# LoRa_Node.net
KiCad netlist of a schematic drawn in Altium Designer
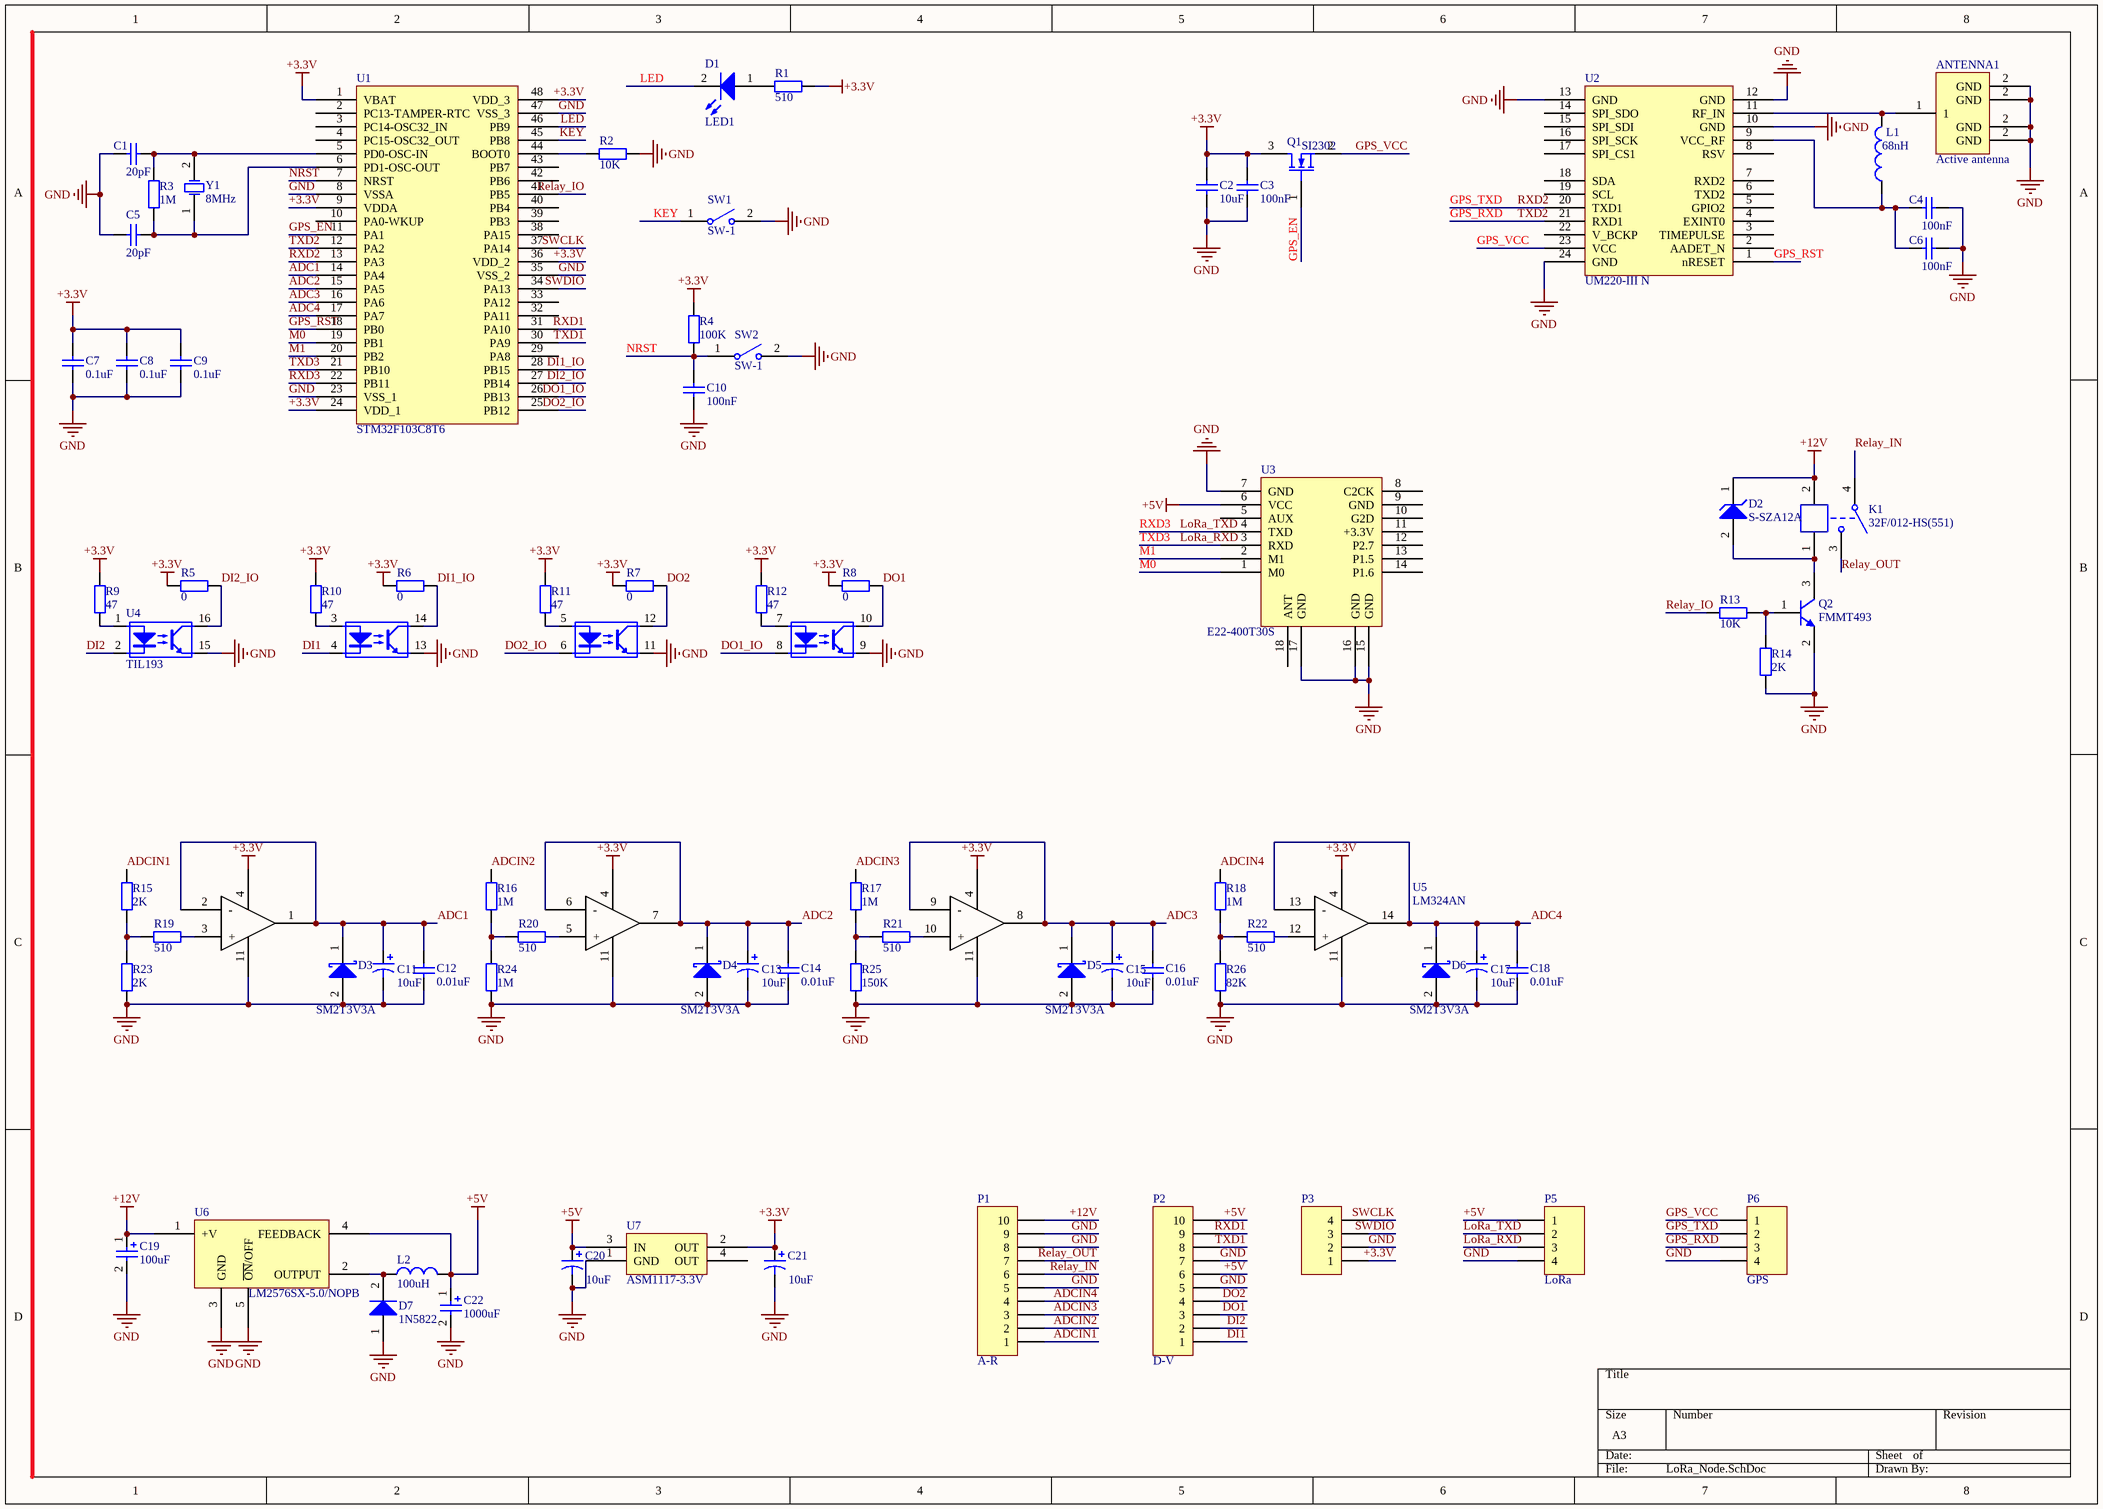
[diagram p0: LoRa_Node.SchDoc]

(export (version "E")
  (design (tool "Eeschema 10.0.6"))
  (components
    (comp (ref "ANTENNA1")
      (value "Active antenna")
      (footprint "SMA-W")
      (libsource (lib "WuRenSouJiu") (part "Active antenna"))
    )
    (comp (ref "C1")
      (value "20pF")
      (footprint "0603C")
      (description "Capacitor")
      (fields (field (name "Comment") "Cap8") (field (name "PUBLISHER") "Altium Limited"))
      (libsource (lib "Miscellaneous Devices") (part "Cap"))
    )
    (comp (ref "C2")
      (value "10uF")
      (footprint "0603C")
      (description "Capacitor")
      (fields (field (name "Comment") "Cap15") (field (name "PUBLISHER") "Altium Limited"))
      (libsource (lib "Miscellaneous Devices") (part "Cap"))
    )
    (comp (ref "C3")
      (value "100nF")
      (footprint "0603C")
      (description "Capacitor")
      (fields (field (name "Comment") "Cap16") (field (name "PUBLISHER") "Altium Limited"))
      (libsource (lib "Miscellaneous Devices") (part "Cap"))
    )
    (comp (ref "C4")
      (value "100nF")
      (footprint "0603C")
      (description "Capacitor")
      (fields (field (name "Comment") "Cap17") (field (name "PUBLISHER") "Altium Limited"))
      (libsource (lib "Miscellaneous Devices") (part "Cap"))
    )
    (comp (ref "C5")
      (value "20pF")
      (footprint "0603C")
      (description "Capacitor")
      (fields (field (name "Comment") "Cap9") (field (name "PUBLISHER") "Altium Limited"))
      (libsource (lib "Miscellaneous Devices") (part "Cap"))
    )
    (comp (ref "C6")
      (value "100nF")
      (footprint "0603C")
      (description "Capacitor")
      (fields (field (name "Comment") "Cap18") (field (name "PUBLISHER") "Altium Limited"))
      (libsource (lib "Miscellaneous Devices") (part "Cap"))
    )
    (comp (ref "C7")
      (value "0.1uF")
      (footprint "0603C")
      (description "Capacitor")
      (fields (field (name "Comment") "Cap11") (field (name "PUBLISHER") "Altium Limited"))
      (libsource (lib "Miscellaneous Devices") (part "Cap"))
    )
    (comp (ref "C8")
      (value "0.1uF")
      (footprint "0603C")
      (description "Capacitor")
      (fields (field (name "Comment") "Cap12") (field (name "PUBLISHER") "Altium Limited"))
      (libsource (lib "Miscellaneous Devices") (part "Cap"))
    )
    (comp (ref "C9")
      (value "0.1uF")
      (footprint "0603C")
      (description "Capacitor")
      (fields (field (name "Comment") "Cap13") (field (name "PUBLISHER") "Altium Limited"))
      (libsource (lib "Miscellaneous Devices") (part "Cap"))
    )
    (comp (ref "C10")
      (value "100nF")
      (footprint "0603C")
      (description "Capacitor")
      (fields (field (name "Comment") "Cap10") (field (name "PUBLISHER") "Altium Limited"))
      (libsource (lib "Miscellaneous Devices") (part "Cap"))
    )
    (comp (ref "C11")
      (value "10uF")
      (footprint "0603C")
      (description "Polarized Capacitor (Radial)")
      (fields (field (name "PUBLISHER") "Altium Limited"))
      (libsource (lib "Miscellaneous Devices") (part "Cap Pol1"))
    )
    (comp (ref "C12")
      (value "0.01uF")
      (footprint "0603C")
      (description "无极性电容")
      (fields (field (name "Comment") "Cap") (field (name "PUBLISHER") "Altium Limited"))
      (libsource (lib "18-常用器件") (part "Cap"))
    )
    (comp (ref "C13")
      (value "10uF")
      (footprint "0603C")
      (description "Polarized Capacitor (Radial)")
      (fields (field (name "PUBLISHER") "Altium Limited"))
      (libsource (lib "Miscellaneous Devices") (part "Cap Pol1"))
    )
    (comp (ref "C14")
      (value "0.01uF")
      (footprint "0603C")
      (description "无极性电容")
      (fields (field (name "Comment") "Cap") (field (name "PUBLISHER") "Altium Limited"))
      (libsource (lib "18-常用器件") (part "Cap"))
    )
    (comp (ref "C15")
      (value "10uF")
      (footprint "0603C")
      (description "Polarized Capacitor (Radial)")
      (fields (field (name "PUBLISHER") "Altium Limited"))
      (libsource (lib "Miscellaneous Devices") (part "Cap Pol1"))
    )
    (comp (ref "C16")
      (value "0.01uF")
      (footprint "0603C")
      (description "无极性电容")
      (fields (field (name "Comment") "Cap") (field (name "PUBLISHER") "Altium Limited"))
      (libsource (lib "18-常用器件") (part "Cap"))
    )
    (comp (ref "C17")
      (value "10uF")
      (footprint "0603C")
      (description "Polarized Capacitor (Radial)")
      (fields (field (name "PUBLISHER") "Altium Limited"))
      (libsource (lib "Miscellaneous Devices") (part "Cap Pol1"))
    )
    (comp (ref "C18")
      (value "0.01uF")
      (footprint "0603C")
      (description "无极性电容")
      (fields (field (name "Comment") "Cap") (field (name "PUBLISHER") "Altium Limited"))
      (libsource (lib "18-常用器件") (part "Cap"))
    )
    (comp (ref "C19")
      (value "100uF")
      (footprint "100uF-16V")
      (description "Polarized Capacitor (Axial)")
      (fields (field (name "PUBLISHER") "Altium Limited"))
      (libsource (lib "Miscellaneous Devices") (part "Cap Pol2"))
    )
    (comp (ref "C20")
      (value "10uF")
      (footprint "0603C")
      (description "Polarized Capacitor (Radial)")
      (fields (field (name "PUBLISHER") "Altium Limited"))
      (libsource (lib "Miscellaneous Devices") (part "Cap Pol1"))
    )
    (comp (ref "C21")
      (value "10uF")
      (footprint "0603C")
      (description "Polarized Capacitor (Radial)")
      (fields (field (name "PUBLISHER") "Altium Limited"))
      (libsource (lib "Miscellaneous Devices") (part "Cap Pol1"))
    )
    (comp (ref "C22")
      (value "1000uF")
      (footprint "1000uF-6.3V")
      (description "Polarized Capacitor (Axial)")
      (fields (field (name "PUBLISHER") "Altium Limited"))
      (libsource (lib "Miscellaneous Devices") (part "Cap Pol2"))
    )
    (comp (ref "D1")
      (value "LED1")
      (footprint "D0603")
      (description "Typical RED GaAs LED")
      (fields (field (name "PUBLISHER") "Altium Limited"))
      (libsource (lib "Miscellaneous Devices") (part "LED1"))
    )
    (comp (ref "D2")
      (value "S-SZA12A")
      (footprint "S-SZA12A")
      (description "Zener Diode")
      (fields (field (name "PUBLISHER") "Altium Limited"))
      (libsource (lib "Miscellaneous Devices") (part "D Zener"))
    )
    (comp (ref "D3")
      (value "SM2T3V3A")
      (footprint "3.3V稳压二极管(LMSZ5226BT1G)")
      (description "Schottky Rectifier")
      (fields (field (name "PUBLISHER") "Altium Limited"))
      (libsource (lib "Miscellaneous Devices") (part "Diode 10TQ035"))
    )
    (comp (ref "D4")
      (value "SM2T3V3A")
      (footprint "3.3V稳压二极管(LMSZ5226BT1G)")
      (description "Schottky Rectifier")
      (fields (field (name "PUBLISHER") "Altium Limited"))
      (libsource (lib "Miscellaneous Devices") (part "Diode 10TQ035"))
    )
    (comp (ref "D5")
      (value "SM2T3V3A")
      (footprint "3.3V稳压二极管(LMSZ5226BT1G)")
      (description "Schottky Rectifier")
      (fields (field (name "PUBLISHER") "Altium Limited"))
      (libsource (lib "Miscellaneous Devices") (part "Diode 10TQ035"))
    )
    (comp (ref "D6")
      (value "SM2T3V3A")
      (footprint "3.3V稳压二极管(LMSZ5226BT1G)")
      (description "Schottky Rectifier")
      (fields (field (name "PUBLISHER") "Altium Limited"))
      (libsource (lib "Miscellaneous Devices") (part "Diode 10TQ035"))
    )
    (comp (ref "D7")
      (value "1N5822")
      (footprint "DO-201AD")
      (description "3 Amp Medium Power Silicon Rectifier Diode")
      (fields (field (name "PUBLISHER") "Altium Limited"))
      (libsource (lib "Miscellaneous Devices") (part "Diode 1N5408"))
    )
    (comp (ref "K1")
      (value "32F/012-HS(551)")
      (footprint "32F/012-HS（551）")
      (libsource (lib "7.1   - 继电器") (part "32F/012-HS(551)"))
    )
    (comp (ref "L1")
      (value "68nH")
      (footprint "0603L")
      (description "Inductor")
      (fields (field (name "Comment") "Inductor3") (field (name "PUBLISHER") "Altium Limited"))
      (libsource (lib "Miscellaneous Devices") (part "Inductor"))
    )
    (comp (ref "L2")
      (value "100uH")
      (footprint "L0805")
      (description "电感")
      (fields (field (name "Comment") "Inductor") (field (name "PUBLISHER") "Altium Limited"))
      (libsource (lib "18-常用器件") (part "Inductor"))
    )
    (comp (ref "P1")
      (value "A-R")
      (footprint "HDR2.54-LI-10P")
      (description "Header, 10-Pin")
      (fields (field (name "PUBLISHER") "Altium Limited"))
      (libsource (lib "Miscellaneous Connectors") (part "MHDR1X10"))
    )
    (comp (ref "P2")
      (value "D-V")
      (footprint "HDR2.54-LI-10P")
      (description "Header, 10-Pin")
      (fields (field (name "PUBLISHER") "Altium Limited"))
      (libsource (lib "Miscellaneous Connectors") (part "MHDR1X10"))
    )
    (comp (ref "P3")
      (value "Header 4")
      (footprint "HDR2.54-LI-4P")
      (description "接插件")
      (fields (field (name "PUBLISHER") "Altium Limited"))
      (libsource (lib "18-常用器件") (part "Header 4"))
    )
    (comp (ref "P5")
      (value "LoRa")
      (footprint "HDR2.54-LI-4P")
      (description "Header, 4-Pin")
      (fields (field (name "PUBLISHER") "Altium Limited"))
      (libsource (lib "Miscellaneous Connectors") (part "Header 4"))
    )
    (comp (ref "P6")
      (value "GPS")
      (footprint "HDR2.54-LI-4P")
      (description "Header, 4-Pin")
      (fields (field (name "PUBLISHER") "Altium Limited"))
      (libsource (lib "Miscellaneous Connectors") (part "Header 4"))
    )
    (comp (ref "Q1")
      (value "SI2302")
      (footprint "FMMT493")
      (description "N-Channel MOSFET")
      (fields (field (name "PUBLISHER") "Altium Limited"))
      (libsource (lib "Miscellaneous Devices") (part "MOSFET-N"))
    )
    (comp (ref "Q2")
      (value "FMMT493")
      (footprint "FMMT493")
      (description "NPN三极管")
      (fields (field (name "PUBLISHER") "Altium Limited"))
      (libsource (lib "18-常用器件") (part "S8050"))
    )
    (comp (ref "R1")
      (value "510")
      (footprint "0603R")
      (description "Resistor")
      (fields (field (name "Comment") "Res11") (field (name "PUBLISHER") "Altium Limited"))
      (libsource (lib "Miscellaneous Devices") (part "Res2"))
    )
    (comp (ref "R2")
      (value "10K")
      (footprint "0603R")
      (description "Resistor")
      (fields (field (name "Comment") "Res9") (field (name "PUBLISHER") "Altium Limited"))
      (libsource (lib "") (part "Res2_3"))
    )
    (comp (ref "R3")
      (value "1M")
      (footprint "0603R")
      (description "Resistor")
      (fields (field (name "Comment") "Res8") (field (name "PUBLISHER") "Altium Limited"))
      (libsource (lib "") (part "Res2_2"))
    )
    (comp (ref "R4")
      (value "100K")
      (footprint "0603R")
      (description "Resistor")
      (fields (field (name "Comment") "Res10") (field (name "PUBLISHER") "Altium Limited"))
      (libsource (lib "") (part "Res2_2"))
    )
    (comp (ref "R5")
      (value "0")
      (footprint "0603R")
      (description "贴片电阻")
      (fields (field (name "Comment") "Res1") (field (name "PUBLISHER") "Altium Limited"))
      (libsource (lib "") (part "Res1_1"))
    )
    (comp (ref "R6")
      (value "0")
      (footprint "0603R")
      (description "贴片电阻")
      (fields (field (name "Comment") "Res1") (field (name "PUBLISHER") "Altium Limited"))
      (libsource (lib "") (part "Res1_1"))
    )
    (comp (ref "R7")
      (value "0")
      (footprint "0603R")
      (description "贴片电阻")
      (fields (field (name "Comment") "Res1") (field (name "PUBLISHER") "Altium Limited"))
      (libsource (lib "") (part "Res1_1"))
    )
    (comp (ref "R8")
      (value "0")
      (footprint "0603R")
      (description "贴片电阻")
      (fields (field (name "Comment") "Res1") (field (name "PUBLISHER") "Altium Limited"))
      (libsource (lib "") (part "Res1_1"))
    )
    (comp (ref "R9")
      (value "47")
      (footprint "0603R")
      (description "贴片电阻")
      (fields (field (name "Comment") "Res1") (field (name "PUBLISHER") "Altium Limited"))
      (libsource (lib "18-常用器件") (part "Res1"))
    )
    (comp (ref "R10")
      (value "47")
      (footprint "0603R")
      (description "贴片电阻")
      (fields (field (name "Comment") "Res1") (field (name "PUBLISHER") "Altium Limited"))
      (libsource (lib "18-常用器件") (part "Res1"))
    )
    (comp (ref "R11")
      (value "47")
      (footprint "0603R")
      (description "贴片电阻")
      (fields (field (name "Comment") "Res1") (field (name "PUBLISHER") "Altium Limited"))
      (libsource (lib "18-常用器件") (part "Res1"))
    )
    (comp (ref "R12")
      (value "47")
      (footprint "0603R")
      (description "贴片电阻")
      (fields (field (name "Comment") "Res1") (field (name "PUBLISHER") "Altium Limited"))
      (libsource (lib "18-常用器件") (part "Res1"))
    )
    (comp (ref "R13")
      (value "10K")
      (footprint "0603R")
      (description "Resistor")
      (fields (field (name "Comment") "Res11") (field (name "PUBLISHER") "Altium Limited"))
      (libsource (lib "Miscellaneous Devices") (part "Res2"))
    )
    (comp (ref "R14")
      (value "2K")
      (footprint "0603R")
      (description "Resistor")
      (fields (field (name "Comment") "Res11") (field (name "PUBLISHER") "Altium Limited"))
      (libsource (lib "") (part "Res2_1"))
    )
    (comp (ref "R15")
      (value "2K")
      (footprint "0603R")
      (description "贴片电阻")
      (fields (field (name "Comment") "Res1") (field (name "PUBLISHER") "Altium Limited"))
      (libsource (lib "18-常用器件") (part "Res1"))
    )
    (comp (ref "R16")
      (value "1M")
      (footprint "0603R")
      (description "贴片电阻")
      (fields (field (name "Comment") "Res1") (field (name "PUBLISHER") "Altium Limited"))
      (libsource (lib "18-常用器件") (part "Res1"))
    )
    (comp (ref "R17")
      (value "1M")
      (footprint "0603R")
      (description "贴片电阻")
      (fields (field (name "Comment") "Res1") (field (name "PUBLISHER") "Altium Limited"))
      (libsource (lib "18-常用器件") (part "Res1"))
    )
    (comp (ref "R18")
      (value "1M")
      (footprint "0603R")
      (description "贴片电阻")
      (fields (field (name "Comment") "Res1") (field (name "PUBLISHER") "Altium Limited"))
      (libsource (lib "18-常用器件") (part "Res1"))
    )
    (comp (ref "R19")
      (value "510")
      (footprint "0603R")
      (description "贴片电阻")
      (fields (field (name "Comment") "Res1") (field (name "PUBLISHER") "Altium Limited"))
      (libsource (lib "") (part "Res1_1"))
    )
    (comp (ref "R20")
      (value "510")
      (footprint "0603R")
      (description "贴片电阻")
      (fields (field (name "Comment") "Res1") (field (name "PUBLISHER") "Altium Limited"))
      (libsource (lib "") (part "Res1_1"))
    )
    (comp (ref "R21")
      (value "510")
      (footprint "0603R")
      (description "贴片电阻")
      (fields (field (name "Comment") "Res1") (field (name "PUBLISHER") "Altium Limited"))
      (libsource (lib "") (part "Res1_1"))
    )
    (comp (ref "R22")
      (value "510")
      (footprint "0603R")
      (description "贴片电阻")
      (fields (field (name "Comment") "Res1") (field (name "PUBLISHER") "Altium Limited"))
      (libsource (lib "") (part "Res1_1"))
    )
    (comp (ref "R23")
      (value "2K")
      (footprint "0603R")
      (description "贴片电阻")
      (fields (field (name "Comment") "Res1") (field (name "PUBLISHER") "Altium Limited"))
      (libsource (lib "18-常用器件") (part "Res1"))
    )
    (comp (ref "R24")
      (value "1M")
      (footprint "0603R")
      (description "贴片电阻")
      (fields (field (name "Comment") "Res1") (field (name "PUBLISHER") "Altium Limited"))
      (libsource (lib "18-常用器件") (part "Res1"))
    )
    (comp (ref "R25")
      (value "150K")
      (footprint "0603R")
      (description "贴片电阻")
      (fields (field (name "Comment") "Res1") (field (name "PUBLISHER") "Altium Limited"))
      (libsource (lib "18-常用器件") (part "Res1"))
    )
    (comp (ref "R26")
      (value "82K")
      (footprint "0603R")
      (description "贴片电阻")
      (fields (field (name "Comment") "Res1") (field (name "PUBLISHER") "Altium Limited"))
      (libsource (lib "18-常用器件") (part "Res1"))
    )
    (comp (ref "SW1") (value "SW-1") (footprint "SW-1") (libsource (lib "WuRenSouJiu") (part "SW-1")))
    (comp (ref "SW2") (value "SW-1") (footprint "SW-1") (libsource (lib "WuRenSouJiu") (part "SW-1")))
    (comp (ref "U1")
      (value "STM32F103C8T6")
      (footprint "stm32l151c8t6")
      (libsource (lib "WuRenSouJiu") (part "STM32F103C8T6"))
    )
    (comp (ref "U2")
      (value "UM220-III N")
      (footprint "UM220-III")
      (libsource (lib "WuRenSouJiu") (part "UM220-III N"))
    )
    (comp (ref "U3")
      (value "E22-400T30S")
      (footprint "PE32(915T30S)")
      (libsource (lib "WuRenSouJiu") (part "E22-400T30S"))
    )
    (comp (ref "U4") (value "TIL193") (footprint "DIP16") (libsource (lib "光电器件") (part "TIL93")))
    (comp (ref "U5") (value "LM324AN") (footprint "LM324AN") (libsource (lib "18-常用器件") (part "LM324AN")))
    (comp (ref "U6")
      (value "LM2576SX-5.0/NOPB")
      (footprint "LM2576SX-5.0/NOPB")
      (libsource (lib "18-常用器件") (part "LM2576SX-5.0/NOPB"))
    )
    (comp (ref "U7")
      (value "ASM1117-3.3V")
      (footprint "SOT-223")
      (description "3.3V稳压芯片")
      (libsource (lib "18-常用器件") (part "ASM1117"))
    )
    (comp (ref "Y1")
      (value "8MHz")
      (footprint "XTAL")
      (description "Crystal Oscillator")
      (fields (field (name "PUBLISHER") "Altium Limited"))
      (libsource (lib "Miscellaneous Devices") (part "XTAL"))
    )
  )
  (nets
    (net (code "1") (name "+3.3V") (class "Default")
      (node (ref "C2") (pin "1") (pinfunction "1_1") (pintype "passive"))
      (node (ref "C21") (pin "1") (pinfunction "1_1") (pintype "passive"))
      (node (ref "C3") (pin "1") (pinfunction "1_1") (pintype "passive"))
      (node (ref "C7") (pin "1") (pinfunction "1_1") (pintype "passive"))
      (node (ref "C8") (pin "1") (pinfunction "1_1") (pintype "passive"))
      (node (ref "C9") (pin "1") (pinfunction "1_1") (pintype "passive"))
      (node (ref "P3") (pin "1") (pinfunction "1_1") (pintype "passive"))
      (node (ref "Q1") (pin "3") (pinfunction "D_3") (pintype "passive"))
      (node (ref "R1") (pin "1") (pinfunction "1_1") (pintype "passive"))
      (node (ref "R10") (pin "2") (pinfunction "2_2") (pintype "passive"))
      (node (ref "R11") (pin "2") (pinfunction "2_2") (pintype "passive"))
      (node (ref "R12") (pin "2") (pinfunction "2_2") (pintype "passive"))
      (node (ref "R4") (pin "2") (pinfunction "2_2") (pintype "passive"))
      (node (ref "R5") (pin "2") (pinfunction "2_2") (pintype "passive"))
      (node (ref "R6") (pin "2") (pinfunction "2_2") (pintype "passive"))
      (node (ref "R7") (pin "2") (pinfunction "2_2") (pintype "passive"))
      (node (ref "R8") (pin "2") (pinfunction "2_2") (pintype "passive"))
      (node (ref "R9") (pin "2") (pinfunction "2_2") (pintype "passive"))
      (node (ref "U1") (pin "1") (pinfunction "VBAT_1") (pintype "passive"))
      (node (ref "U1") (pin "24") (pinfunction "VDD_1_24") (pintype "passive"))
      (node (ref "U1") (pin "36") (pinfunction "VDD_2_36") (pintype "passive"))
      (node (ref "U1") (pin "48") (pinfunction "VDD_3_48") (pintype "passive"))
      (node (ref "U1") (pin "9") (pinfunction "VDDA_9") (pintype "passive"))
      (node (ref "U5") (pin "4") (pintype "passive"))
      (node (ref "U7") (pin "2") (pinfunction "OUT_2") (pintype "passive"))
    )
    (net (code "2") (name "+5V") (class "Default")
      (node (ref "C20") (pin "1") (pinfunction "1_1") (pintype "passive"))
      (node (ref "C22") (pin "1") (pinfunction "1_1") (pintype "passive"))
      (node (ref "L2") (pin "2") (pinfunction "2_2") (pintype "passive"))
      (node (ref "P2") (pin "10") (pinfunction "10_10") (pintype "passive"))
      (node (ref "P2") (pin "6") (pinfunction "6_6") (pintype "passive"))
      (node (ref "P5") (pin "1") (pinfunction "1_1") (pintype "passive"))
      (node (ref "U3") (pin "6") (pinfunction "VCC_6") (pintype "passive"))
      (node (ref "U6") (pin "4") (pinfunction "FEEDBACK_4") (pintype "passive"))
      (node (ref "U7") (pin "3") (pinfunction "IN_3") (pintype "passive"))
    )
    (net (code "3") (name "+12V") (class "Default")
      (node (ref "C19") (pin "1") (pinfunction "1_1") (pintype "passive"))
      (node (ref "D2") (pin "1") (pinfunction "K_1") (pintype "passive"))
      (node (ref "K1") (pin "2") (pinfunction "2_2") (pintype "passive"))
      (node (ref "P1") (pin "10") (pinfunction "10_10") (pintype "passive"))
      (node (ref "U6") (pin "1") (pinfunction "+V_1") (pintype "passive"))
    )
    (net (code "4") (name "/ADC1") (class "Default")
      (node (ref "C11") (pin "1") (pinfunction "1_1") (pintype "passive"))
      (node (ref "C12") (pin "2") (pinfunction "2_2") (pintype "passive"))
      (node (ref "D3") (pin "1") (pinfunction "K_1") (pintype "passive"))
      (node (ref "U1") (pin "14") (pinfunction "PA4_14") (pintype "passive"))
      (node (ref "U5") (pin "1") (pintype "passive"))
      (node (ref "U5") (pin "2") (pinfunction "-_2") (pintype "passive"))
    )
    (net (code "5") (name "/ADC2") (class "Default")
      (node (ref "C13") (pin "1") (pinfunction "1_1") (pintype "passive"))
      (node (ref "C14") (pin "2") (pinfunction "2_2") (pintype "passive"))
      (node (ref "D4") (pin "1") (pinfunction "K_1") (pintype "passive"))
      (node (ref "U1") (pin "15") (pinfunction "PA5_15") (pintype "passive"))
      (node (ref "U5") (pin "6") (pinfunction "-_6") (pintype "passive"))
      (node (ref "U5") (pin "7") (pintype "passive"))
    )
    (net (code "6") (name "/ADC3") (class "Default")
      (node (ref "C15") (pin "1") (pinfunction "1_1") (pintype "passive"))
      (node (ref "C16") (pin "2") (pinfunction "2_2") (pintype "passive"))
      (node (ref "D5") (pin "1") (pinfunction "K_1") (pintype "passive"))
      (node (ref "U1") (pin "16") (pinfunction "PA6_16") (pintype "passive"))
      (node (ref "U5") (pin "8") (pintype "passive"))
      (node (ref "U5") (pin "9") (pinfunction "-_9") (pintype "passive"))
    )
    (net (code "7") (name "/ADC4") (class "Default")
      (node (ref "C17") (pin "1") (pinfunction "1_1") (pintype "passive"))
      (node (ref "C18") (pin "2") (pinfunction "2_2") (pintype "passive"))
      (node (ref "D6") (pin "1") (pinfunction "K_1") (pintype "passive"))
      (node (ref "U1") (pin "17") (pinfunction "PA7_17") (pintype "passive"))
      (node (ref "U5") (pin "13") (pinfunction "-_13") (pintype "passive"))
      (node (ref "U5") (pin "14") (pintype "passive"))
    )
    (net (code "8") (name "/ADCIN1") (class "Default")
      (node (ref "P1") (pin "1") (pinfunction "1_1") (pintype "passive"))
      (node (ref "R15") (pin "2") (pinfunction "2_2") (pintype "passive"))
    )
    (net (code "9") (name "/ADCIN2") (class "Default")
      (node (ref "P1") (pin "2") (pinfunction "2_2") (pintype "passive"))
      (node (ref "R16") (pin "2") (pinfunction "2_2") (pintype "passive"))
    )
    (net (code "10") (name "/ADCIN3") (class "Default")
      (node (ref "P1") (pin "3") (pinfunction "3_3") (pintype "passive"))
      (node (ref "R17") (pin "2") (pinfunction "2_2") (pintype "passive"))
    )
    (net (code "11") (name "/ADCIN4") (class "Default")
      (node (ref "P1") (pin "4") (pinfunction "4_4") (pintype "passive"))
      (node (ref "R18") (pin "2") (pinfunction "2_2") (pintype "passive"))
    )
    (net (code "12") (name "/DI1") (class "Default")
      (node (ref "P2") (pin "1") (pinfunction "1_1") (pintype "passive"))
      (node (ref "U4") (pin "4") (pinfunction "LED_Cathode_4") (pintype "passive"))
    )
    (net (code "13") (name "/DI1_IO") (class "Default")
      (node (ref "R6") (pin "1") (pinfunction "1_1") (pintype "passive"))
      (node (ref "U1") (pin "28") (pinfunction "PB15_28") (pintype "passive"))
      (node (ref "U4") (pin "14") (pinfunction "Collector_14") (pintype "passive"))
    )
    (net (code "14") (name "/DI2") (class "Default")
      (node (ref "P2") (pin "2") (pinfunction "2_2") (pintype "passive"))
      (node (ref "U4") (pin "2") (pinfunction "LED_Cathode_2") (pintype "passive"))
    )
    (net (code "15") (name "/DI2_IO") (class "Default")
      (node (ref "R5") (pin "1") (pinfunction "1_1") (pintype "passive"))
      (node (ref "U1") (pin "27") (pinfunction "PB14_27") (pintype "passive"))
      (node (ref "U4") (pin "16") (pinfunction "Collector_16") (pintype "passive"))
    )
    (net (code "16") (name "/DO1") (class "Default")
      (node (ref "P2") (pin "3") (pinfunction "3_3") (pintype "passive"))
      (node (ref "R8") (pin "1") (pinfunction "1_1") (pintype "passive"))
      (node (ref "U4") (pin "10") (pinfunction "Collector_10") (pintype "passive"))
    )
    (net (code "17") (name "/DO1_IO") (class "Default")
      (node (ref "U1") (pin "26") (pinfunction "PB13_26") (pintype "passive"))
      (node (ref "U4") (pin "8") (pinfunction "LED_Cathode_8") (pintype "passive"))
    )
    (net (code "18") (name "/DO2") (class "Default")
      (node (ref "P2") (pin "4") (pinfunction "4_4") (pintype "passive"))
      (node (ref "R7") (pin "1") (pinfunction "1_1") (pintype "passive"))
      (node (ref "U4") (pin "12") (pinfunction "Collector_12") (pintype "passive"))
    )
    (net (code "19") (name "/DO2_IO") (class "Default")
      (node (ref "U1") (pin "25") (pinfunction "PB12_25") (pintype "passive"))
      (node (ref "U4") (pin "6") (pinfunction "LED_Cathode_6") (pintype "passive"))
    )
    (net (code "20") (name "/GPS_EN") (class "Default")
      (node (ref "Q1") (pin "1") (pinfunction "G_1") (pintype "passive"))
      (node (ref "U1") (pin "11") (pinfunction "PA1_11") (pintype "passive"))
    )
    (net (code "21") (name "/GPS_RST") (class "Default")
      (node (ref "U1") (pin "18") (pinfunction "PB0_18") (pintype "passive"))
      (node (ref "U2") (pin "1") (pinfunction "nRESET_1") (pintype "passive"))
    )
    (net (code "22") (name "/GPS_RXD") (class "Default")
      (node (ref "P6") (pin "3") (pinfunction "3_3") (pintype "passive"))
      (node (ref "U1") (pin "12") (pinfunction "PA2_12") (pintype "passive"))
      (node (ref "U2") (pin "21") (pinfunction "RXD1_21") (pintype "passive"))
    )
    (net (code "23") (name "/GPS_TXD") (class "Default")
      (node (ref "P6") (pin "2") (pinfunction "2_2") (pintype "passive"))
      (node (ref "U1") (pin "13") (pinfunction "PA3_13") (pintype "passive"))
      (node (ref "U2") (pin "20") (pinfunction "TXD1_20") (pintype "passive"))
    )
    (net (code "24") (name "/GPS_VCC") (class "Default")
      (node (ref "P6") (pin "1") (pinfunction "1_1") (pintype "passive"))
      (node (ref "Q1") (pin "2") (pinfunction "S_2") (pintype "passive"))
      (node (ref "U2") (pin "23") (pinfunction "VCC_23") (pintype "passive"))
    )
    (net (code "25") (name "/KEY") (class "Default")
      (node (ref "SW1") (pin "1") (pinfunction "COMMON_1") (pintype "passive"))
      (node (ref "U1") (pin "45") (pinfunction "PB8_45") (pintype "passive"))
    )
    (net (code "26") (name "/LED") (class "Default")
      (node (ref "D1") (pin "2") (pinfunction "K_2") (pintype "passive"))
      (node (ref "U1") (pin "46") (pinfunction "PB9_46") (pintype "passive"))
    )
    (net (code "27") (name "/LoRa_RXD") (class "Default")
      (node (ref "P5") (pin "3") (pinfunction "3_3") (pintype "passive"))
      (node (ref "U1") (pin "21") (pinfunction "PB10_21") (pintype "passive"))
      (node (ref "U3") (pin "3") (pinfunction "RXD_3") (pintype "passive"))
    )
    (net (code "28") (name "/LoRa_TXD") (class "Default")
      (node (ref "P5") (pin "2") (pinfunction "2_2") (pintype "passive"))
      (node (ref "U1") (pin "22") (pinfunction "PB11_22") (pintype "passive"))
      (node (ref "U3") (pin "4") (pinfunction "TXD_4") (pintype "passive"))
    )
    (net (code "29") (name "/M0") (class "Default")
      (node (ref "U1") (pin "19") (pinfunction "PB1_19") (pintype "passive"))
      (node (ref "U3") (pin "1") (pinfunction "M0_1") (pintype "passive"))
    )
    (net (code "30") (name "/M1") (class "Default")
      (node (ref "U1") (pin "20") (pinfunction "PB2_20") (pintype "passive"))
      (node (ref "U3") (pin "2") (pinfunction "M1_2") (pintype "passive"))
    )
    (net (code "31") (name "/NRST") (class "Default")
      (node (ref "C10") (pin "1") (pinfunction "1_1") (pintype "passive"))
      (node (ref "R4") (pin "1") (pinfunction "1_1") (pintype "passive"))
      (node (ref "SW2") (pin "1") (pinfunction "COMMON_1") (pintype "passive"))
      (node (ref "U1") (pin "7") (pinfunction "NRST_7") (pintype "passive"))
    )
    (net (code "32") (name "/RXD1") (class "Default")
      (node (ref "P2") (pin "9") (pinfunction "9_9") (pintype "passive"))
      (node (ref "U1") (pin "31") (pinfunction "PA10_31") (pintype "passive"))
    )
    (net (code "33") (name "/Relay_IN") (class "Default")
      (node (ref "K1") (pin "4") (pinfunction "4_4") (pintype "passive"))
      (node (ref "P1") (pin "6") (pinfunction "6_6") (pintype "passive"))
    )
    (net (code "34") (name "/Relay_IO") (class "Default")
      (node (ref "R13") (pin "2") (pinfunction "2_2") (pintype "passive"))
      (node (ref "U1") (pin "41") (pinfunction "PB5_41") (pintype "passive"))
    )
    (net (code "35") (name "/Relay_OUT") (class "Default")
      (node (ref "K1") (pin "3") (pinfunction "3_3") (pintype "passive"))
      (node (ref "P1") (pin "7") (pinfunction "7_7") (pintype "passive"))
    )
    (net (code "36") (name "/SWCLK") (class "Default")
      (node (ref "P3") (pin "4") (pinfunction "4_4") (pintype "passive"))
      (node (ref "U1") (pin "37") (pinfunction "PA14_37") (pintype "passive"))
    )
    (net (code "37") (name "/SWDIO") (class "Default")
      (node (ref "P3") (pin "3") (pinfunction "3_3") (pintype "passive"))
      (node (ref "U1") (pin "34") (pinfunction "PA13_34") (pintype "passive"))
    )
    (net (code "38") (name "/TXD1") (class "Default")
      (node (ref "P2") (pin "8") (pinfunction "8_8") (pintype "passive"))
      (node (ref "U1") (pin "30") (pinfunction "PA9_30") (pintype "passive"))
    )
    (net (code "39") (name "GND") (class "Default")
      (node (ref "ANTENNA1") (pin "2") (pinfunction "GND_2") (pintype "passive"))
      (node (ref "C1") (pin "2") (pinfunction "2_2") (pintype "passive"))
      (node (ref "C10") (pin "2") (pinfunction "2_2") (pintype "passive"))
      (node (ref "C11") (pin "2") (pinfunction "2_2") (pintype "passive"))
      (node (ref "C12") (pin "1") (pinfunction "1_1") (pintype "passive"))
      (node (ref "C13") (pin "2") (pinfunction "2_2") (pintype "passive"))
      (node (ref "C14") (pin "1") (pinfunction "1_1") (pintype "passive"))
      (node (ref "C15") (pin "2") (pinfunction "2_2") (pintype "passive"))
      (node (ref "C16") (pin "1") (pinfunction "1_1") (pintype "passive"))
      (node (ref "C17") (pin "2") (pinfunction "2_2") (pintype "passive"))
      (node (ref "C18") (pin "1") (pinfunction "1_1") (pintype "passive"))
      (node (ref "C19") (pin "2") (pinfunction "2_2") (pintype "passive"))
      (node (ref "C2") (pin "2") (pinfunction "2_2") (pintype "passive"))
      (node (ref "C20") (pin "2") (pinfunction "2_2") (pintype "passive"))
      (node (ref "C21") (pin "2") (pinfunction "2_2") (pintype "passive"))
      (node (ref "C22") (pin "2") (pinfunction "2_2") (pintype "passive"))
      (node (ref "C3") (pin "2") (pinfunction "2_2") (pintype "passive"))
      (node (ref "C4") (pin "2") (pinfunction "2_2") (pintype "passive"))
      (node (ref "C5") (pin "2") (pinfunction "2_2") (pintype "passive"))
      (node (ref "C6") (pin "2") (pinfunction "2_2") (pintype "passive"))
      (node (ref "C7") (pin "2") (pinfunction "2_2") (pintype "passive"))
      (node (ref "C8") (pin "2") (pinfunction "2_2") (pintype "passive"))
      (node (ref "C9") (pin "2") (pinfunction "2_2") (pintype "passive"))
      (node (ref "D3") (pin "2") (pinfunction "A_2") (pintype "passive"))
      (node (ref "D4") (pin "2") (pinfunction "A_2") (pintype "passive"))
      (node (ref "D5") (pin "2") (pinfunction "A_2") (pintype "passive"))
      (node (ref "D6") (pin "2") (pinfunction "A_2") (pintype "passive"))
      (node (ref "D7") (pin "1") (pinfunction "+_1") (pintype "passive"))
      (node (ref "P1") (pin "5") (pinfunction "5_5") (pintype "passive"))
      (node (ref "P1") (pin "8") (pinfunction "8_8") (pintype "passive"))
      (node (ref "P1") (pin "9") (pinfunction "9_9") (pintype "passive"))
      (node (ref "P2") (pin "5") (pinfunction "5_5") (pintype "passive"))
      (node (ref "P2") (pin "7") (pinfunction "7_7") (pintype "passive"))
      (node (ref "P3") (pin "2") (pinfunction "2_2") (pintype "passive"))
      (node (ref "P5") (pin "4") (pinfunction "4_4") (pintype "passive"))
      (node (ref "P6") (pin "4") (pinfunction "4_4") (pintype "passive"))
      (node (ref "Q2") (pin "2") (pinfunction "E_2") (pintype "passive"))
      (node (ref "R14") (pin "2") (pinfunction "2_2") (pintype "passive"))
      (node (ref "R2") (pin "2") (pinfunction "2_2") (pintype "passive"))
      (node (ref "R23") (pin "1") (pinfunction "1_1") (pintype "passive"))
      (node (ref "R24") (pin "1") (pinfunction "1_1") (pintype "passive"))
      (node (ref "R25") (pin "1") (pinfunction "1_1") (pintype "passive"))
      (node (ref "R26") (pin "1") (pinfunction "1_1") (pintype "passive"))
      (node (ref "SW1") (pin "2") (pinfunction "COMMON_2") (pintype "passive"))
      (node (ref "SW2") (pin "2") (pinfunction "COMMON_2") (pintype "passive"))
      (node (ref "U1") (pin "23") (pinfunction "VSS_1_23") (pintype "passive"))
      (node (ref "U1") (pin "35") (pinfunction "VSS_2_35") (pintype "passive"))
      (node (ref "U1") (pin "47") (pinfunction "VSS_3_47") (pintype "passive"))
      (node (ref "U1") (pin "8") (pinfunction "VSSA_8") (pintype "passive"))
      (node (ref "U2") (pin "10") (pinfunction "GND_10") (pintype "passive"))
      (node (ref "U2") (pin "12") (pinfunction "GND_12") (pintype "passive"))
      (node (ref "U2") (pin "13") (pinfunction "GND_13") (pintype "passive"))
      (node (ref "U2") (pin "24") (pinfunction "GND_24") (pintype "passive"))
      (node (ref "U3") (pin "15") (pinfunction "GND_15") (pintype "passive"))
      (node (ref "U3") (pin "16") (pinfunction "GND_16") (pintype "passive"))
      (node (ref "U3") (pin "17") (pinfunction "GND_17") (pintype "passive"))
      (node (ref "U3") (pin "7") (pinfunction "GND_7") (pintype "passive"))
      (node (ref "U4") (pin "11") (pinfunction "Emitter_11") (pintype "passive"))
      (node (ref "U4") (pin "13") (pinfunction "Emitter_13") (pintype "passive"))
      (node (ref "U4") (pin "15") (pinfunction "Emitter_15") (pintype "passive"))
      (node (ref "U4") (pin "9") (pinfunction "Emitter_9") (pintype "passive"))
      (node (ref "U5") (pin "11") (pintype "passive"))
      (node (ref "U6") (pin "3") (pinfunction "GND_3") (pintype "passive"))
      (node (ref "U6") (pin "5") (pinfunction "~{ON}/OFF_5") (pintype "passive"))
      (node (ref "U7") (pin "1") (pinfunction "GND_1") (pintype "passive"))
    )
    (net (code "40") (name "Net-(D1-A)") (class "Default")
      (node (ref "D1") (pin "1") (pinfunction "A_1") (pintype "passive"))
      (node (ref "R1") (pin "2") (pinfunction "2_2") (pintype "passive"))
    )
    (net (code "41") (name "Net-(D2-A)") (class "Default")
      (node (ref "D2") (pin "2") (pinfunction "A_2") (pintype "passive"))
      (node (ref "K1") (pin "1") (pinfunction "1_1") (pintype "passive"))
      (node (ref "Q2") (pin "3") (pinfunction "C_3") (pintype "passive"))
    )
    (net (code "42") (name "Net-(D7--)") (class "Default")
      (node (ref "D7") (pin "2") (pinfunction "-_2") (pintype "passive"))
      (node (ref "L2") (pin "1") (pinfunction "1_1") (pintype "passive"))
      (node (ref "U6") (pin "2") (pinfunction "OUTPUT_2") (pintype "passive"))
    )
    (net (code "43") (name "Net-(Q2-B)") (class "Default")
      (node (ref "Q2") (pin "1") (pinfunction "B_1") (pintype "passive"))
      (node (ref "R13") (pin "1") (pinfunction "1_1") (pintype "passive"))
      (node (ref "R14") (pin "1") (pinfunction "1_1") (pintype "passive"))
    )
    (net (code "44") (name "Net-(R9-Pad1)") (class "Default")
      (node (ref "R9") (pin "1") (pinfunction "1_1") (pintype "passive"))
      (node (ref "U4") (pin "1") (pinfunction "LED_Anode_1") (pintype "passive"))
    )
    (net (code "45") (name "Net-(R10-Pad1)") (class "Default")
      (node (ref "R10") (pin "1") (pinfunction "1_1") (pintype "passive"))
      (node (ref "U4") (pin "3") (pinfunction "LED_Anode_3") (pintype "passive"))
    )
    (net (code "46") (name "Net-(R11-Pad1)") (class "Default")
      (node (ref "R11") (pin "1") (pinfunction "1_1") (pintype "passive"))
      (node (ref "U4") (pin "5") (pinfunction "LED_Anode_5") (pintype "passive"))
    )
    (net (code "47") (name "Net-(R12-Pad1)") (class "Default")
      (node (ref "R12") (pin "1") (pinfunction "1_1") (pintype "passive"))
      (node (ref "U4") (pin "7") (pinfunction "LED_Anode_7") (pintype "passive"))
    )
    (net (code "48") (name "Net-(R15-Pad1)") (class "Default")
      (node (ref "R15") (pin "1") (pinfunction "1_1") (pintype "passive"))
      (node (ref "R19") (pin "2") (pinfunction "2_2") (pintype "passive"))
      (node (ref "R23") (pin "2") (pinfunction "2_2") (pintype "passive"))
    )
    (net (code "49") (name "Net-(R16-Pad1)") (class "Default")
      (node (ref "R16") (pin "1") (pinfunction "1_1") (pintype "passive"))
      (node (ref "R20") (pin "2") (pinfunction "2_2") (pintype "passive"))
      (node (ref "R24") (pin "2") (pinfunction "2_2") (pintype "passive"))
    )
    (net (code "50") (name "Net-(R17-Pad1)") (class "Default")
      (node (ref "R17") (pin "1") (pinfunction "1_1") (pintype "passive"))
      (node (ref "R21") (pin "2") (pinfunction "2_2") (pintype "passive"))
      (node (ref "R25") (pin "2") (pinfunction "2_2") (pintype "passive"))
    )
    (net (code "51") (name "Net-(R18-Pad1)") (class "Default")
      (node (ref "R18") (pin "1") (pinfunction "1_1") (pintype "passive"))
      (node (ref "R22") (pin "2") (pinfunction "2_2") (pintype "passive"))
      (node (ref "R26") (pin "2") (pinfunction "2_2") (pintype "passive"))
    )
    (net (code "52") (name "Net-(R19-Pad1)") (class "Default")
      (node (ref "R19") (pin "1") (pinfunction "1_1") (pintype "passive"))
      (node (ref "U5") (pin "3") (pinfunction "+_3") (pintype "passive"))
    )
    (net (code "53") (name "Net-(R20-Pad1)") (class "Default")
      (node (ref "R20") (pin "1") (pinfunction "1_1") (pintype "passive"))
      (node (ref "U5") (pin "5") (pinfunction "+_5") (pintype "passive"))
    )
    (net (code "54") (name "Net-(R21-Pad1)") (class "Default")
      (node (ref "R21") (pin "1") (pinfunction "1_1") (pintype "passive"))
      (node (ref "U5") (pin "10") (pinfunction "+_10") (pintype "passive"))
    )
    (net (code "55") (name "Net-(R22-Pad1)") (class "Default")
      (node (ref "R22") (pin "1") (pinfunction "1_1") (pintype "passive"))
      (node (ref "U5") (pin "12") (pinfunction "+_12") (pintype "passive"))
    )
    (net (code "56") (name "Net-(U1-BOOT0)") (class "Default")
      (node (ref "R2") (pin "1") (pinfunction "1_1") (pintype "passive"))
      (node (ref "U1") (pin "44") (pinfunction "BOOT0_44") (pintype "passive"))
    )
    (net (code "57") (name "Net-(U1-PD0-OSC-IN)") (class "Default")
      (node (ref "C1") (pin "1") (pinfunction "1_1") (pintype "passive"))
      (node (ref "R3") (pin "2") (pinfunction "2_2") (pintype "passive"))
      (node (ref "U1") (pin "5") (pinfunction "PD0-OSC-IN_5") (pintype "passive"))
      (node (ref "Y1") (pin "2") (pinfunction "OSC2_2") (pintype "passive"))
    )
    (net (code "58") (name "Net-(U1-PD1-OSC-OUT)") (class "Default")
      (node (ref "C5") (pin "1") (pinfunction "1_1") (pintype "passive"))
      (node (ref "R3") (pin "1") (pinfunction "1_1") (pintype "passive"))
      (node (ref "U1") (pin "6") (pinfunction "PD1-OSC-OUT_6") (pintype "passive"))
      (node (ref "Y1") (pin "1") (pinfunction "OSC1_1") (pintype "passive"))
    )
    (net (code "59") (name "Net-(U2-RF_IN)") (class "Default")
      (node (ref "ANTENNA1") (pin "1") (pinfunction "1_1") (pintype "passive"))
      (node (ref "L1") (pin "2") (pinfunction "2_2") (pintype "passive"))
      (node (ref "U2") (pin "11") (pinfunction "RF_IN_11") (pintype "passive"))
    )
    (net (code "60") (name "Net-(U2-VCC_RF)") (class "Default")
      (node (ref "C4") (pin "1") (pinfunction "1_1") (pintype "passive"))
      (node (ref "C6") (pin "1") (pinfunction "1_1") (pintype "passive"))
      (node (ref "L1") (pin "1") (pinfunction "1_1") (pintype "passive"))
      (node (ref "U2") (pin "9") (pinfunction "VCC_RF_9") (pintype "passive"))
    )
    (net (code "61") (name "unconnected-(U1-PA0-WKUP-Pad10)") (class "Default")
      (node (ref "U1") (pin "10") (pinfunction "PA0-WKUP_10") (pintype "passive"))
    )
    (net (code "62") (name "unconnected-(U1-PA8-Pad29)") (class "Default")
      (node (ref "U1") (pin "29") (pinfunction "PA8_29") (pintype "passive"))
    )
    (net (code "63") (name "unconnected-(U1-PA11-Pad32)") (class "Default")
      (node (ref "U1") (pin "32") (pinfunction "PA11_32") (pintype "passive"))
    )
    (net (code "64") (name "unconnected-(U1-PA12-Pad33)") (class "Default")
      (node (ref "U1") (pin "33") (pinfunction "PA12_33") (pintype "passive"))
    )
    (net (code "65") (name "unconnected-(U1-PA15-Pad38)") (class "Default")
      (node (ref "U1") (pin "38") (pinfunction "PA15_38") (pintype "passive"))
    )
    (net (code "66") (name "unconnected-(U1-PB3-Pad39)") (class "Default")
      (node (ref "U1") (pin "39") (pinfunction "PB3_39") (pintype "passive"))
    )
    (net (code "67") (name "unconnected-(U1-PB4-Pad40)") (class "Default")
      (node (ref "U1") (pin "40") (pinfunction "PB4_40") (pintype "passive"))
    )
    (net (code "68") (name "unconnected-(U1-PB6-Pad42)") (class "Default")
      (node (ref "U1") (pin "42") (pinfunction "PB6_42") (pintype "passive"))
    )
    (net (code "69") (name "unconnected-(U1-PB7-Pad43)") (class "Default")
      (node (ref "U1") (pin "43") (pinfunction "PB7_43") (pintype "passive"))
    )
    (net (code "70") (name "unconnected-(U1-PC13-TAMPER-RTC-Pad2)") (class "Default")
      (node (ref "U1") (pin "2") (pinfunction "PC13-TAMPER-RTC_2") (pintype "passive"))
    )
    (net (code "71") (name "unconnected-(U1-PC14-OSC32_IN-Pad3)") (class "Default")
      (node (ref "U1") (pin "3") (pinfunction "PC14-OSC32_IN_3") (pintype "passive"))
    )
    (net (code "72") (name "unconnected-(U1-PC15-OSC32_OUT-Pad4)") (class "Default")
      (node (ref "U1") (pin "4") (pinfunction "PC15-OSC32_OUT_4") (pintype "passive"))
    )
    (net (code "73") (name "unconnected-(U2-AADET_N-Pad2)") (class "Default")
      (node (ref "U2") (pin "2") (pinfunction "AADET_N_2") (pintype "passive"))
    )
    (net (code "74") (name "unconnected-(U2-EXINT0-Pad4)") (class "Default")
      (node (ref "U2") (pin "4") (pinfunction "EXINT0_4") (pintype "passive"))
    )
    (net (code "75") (name "unconnected-(U2-GPIO2-Pad5)") (class "Default")
      (node (ref "U2") (pin "5") (pinfunction "GPIO2_5") (pintype "passive"))
    )
    (net (code "76") (name "unconnected-(U2-RSV-Pad8)") (class "Default")
      (node (ref "U2") (pin "8") (pinfunction "RSV_8") (pintype "passive"))
    )
    (net (code "77") (name "unconnected-(U2-RXD2-Pad7)") (class "Default")
      (node (ref "U2") (pin "7") (pinfunction "RXD2_7") (pintype "passive"))
    )
    (net (code "78") (name "unconnected-(U2-SCL-Pad19)") (class "Default")
      (node (ref "U2") (pin "19") (pinfunction "SCL_19") (pintype "passive"))
    )
    (net (code "79") (name "unconnected-(U2-SDA-Pad18)") (class "Default")
      (node (ref "U2") (pin "18") (pinfunction "SDA_18") (pintype "passive"))
    )
    (net (code "80") (name "unconnected-(U2-SPI_CS1-Pad17)") (class "Default")
      (node (ref "U2") (pin "17") (pinfunction "SPI_CS1_17") (pintype "passive"))
    )
    (net (code "81") (name "unconnected-(U2-SPI_SCK-Pad16)") (class "Default")
      (node (ref "U2") (pin "16") (pinfunction "SPI_SCK_16") (pintype "passive"))
    )
    (net (code "82") (name "unconnected-(U2-SPI_SDI-Pad15)") (class "Default")
      (node (ref "U2") (pin "15") (pinfunction "SPI_SDI_15") (pintype "passive"))
    )
    (net (code "83") (name "unconnected-(U2-SPI_SDO-Pad14)") (class "Default")
      (node (ref "U2") (pin "14") (pinfunction "SPI_SDO_14") (pintype "passive"))
    )
    (net (code "84") (name "unconnected-(U2-TIMEPULSE-Pad3)") (class "Default")
      (node (ref "U2") (pin "3") (pinfunction "TIMEPULSE_3") (pintype "passive"))
    )
    (net (code "85") (name "unconnected-(U2-TXD2-Pad6)") (class "Default")
      (node (ref "U2") (pin "6") (pinfunction "TXD2_6") (pintype "passive"))
    )
    (net (code "86") (name "unconnected-(U2-V_BCKP-Pad22)") (class "Default")
      (node (ref "U2") (pin "22") (pinfunction "V_BCKP_22") (pintype "passive"))
    )
    (net (code "87") (name "unconnected-(U3-+3.3V-Pad11)") (class "Default")
      (node (ref "U3") (pin "11") (pinfunction "+3.3V_11") (pintype "passive"))
    )
    (net (code "88") (name "unconnected-(U3-ANT-Pad18)") (class "Default")
      (node (ref "U3") (pin "18") (pinfunction "ANT_18") (pintype "passive"))
    )
    (net (code "89") (name "unconnected-(U3-AUX-Pad5)") (class "Default")
      (node (ref "U3") (pin "5") (pinfunction "AUX_5") (pintype "passive"))
    )
    (net (code "90") (name "unconnected-(U3-C2CK-Pad8)") (class "Default")
      (node (ref "U3") (pin "8") (pinfunction "C2CK_8") (pintype "passive"))
    )
    (net (code "91") (name "unconnected-(U3-G2D-Pad10)") (class "Default")
      (node (ref "U3") (pin "10") (pinfunction "G2D_10") (pintype "passive"))
    )
    (net (code "92") (name "unconnected-(U3-GND-Pad9)") (class "Default")
      (node (ref "U3") (pin "9") (pinfunction "GND_9") (pintype "passive"))
    )
    (net (code "93") (name "unconnected-(U3-P1.5-Pad13)") (class "Default")
      (node (ref "U3") (pin "13") (pinfunction "P1.5_13") (pintype "passive"))
    )
    (net (code "94") (name "unconnected-(U3-P1.6-Pad14)") (class "Default")
      (node (ref "U3") (pin "14") (pinfunction "P1.6_14") (pintype "passive"))
    )
    (net (code "95") (name "unconnected-(U3-P2.7-Pad12)") (class "Default")
      (node (ref "U3") (pin "12") (pinfunction "P2.7_12") (pintype "passive"))
    )
    (net (code "96") (name "unconnected-(U7-OUT-Pad4)") (class "Default")
      (node (ref "U7") (pin "4") (pinfunction "OUT_4") (pintype "passive"))
    )
  )
)
